# MCU_RS485.net
KiCad netlist of a schematic drawn in Altium Designer
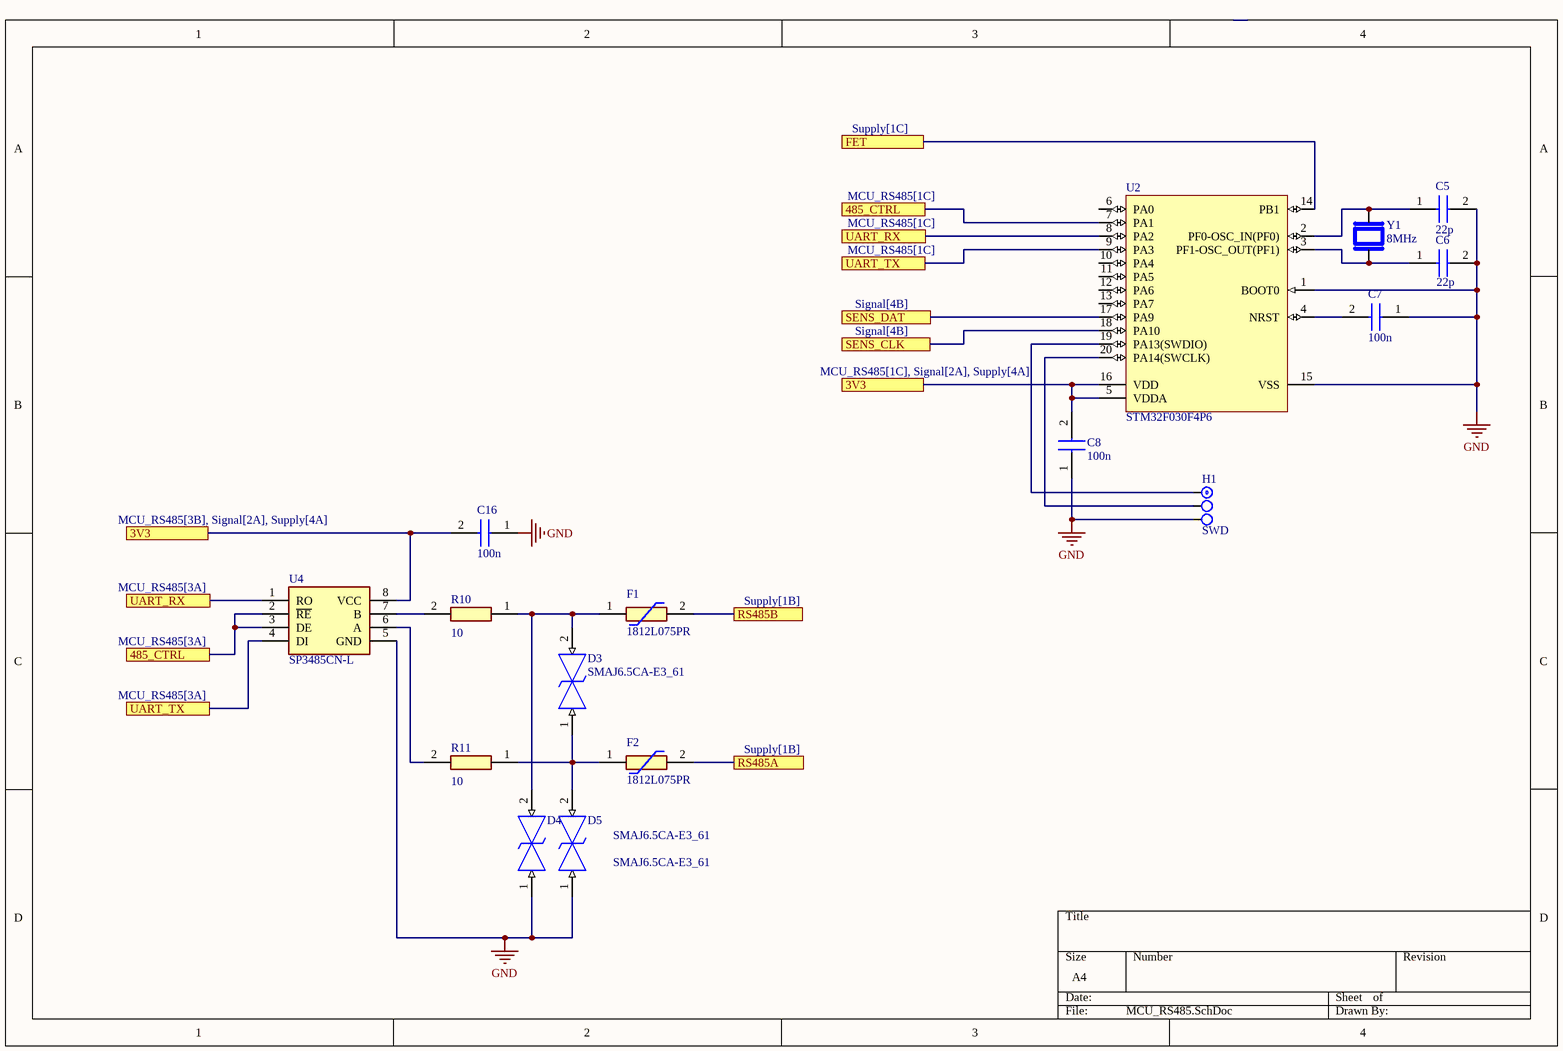
[diagram p0: MCU_RS485.SchDoc]

(export (version "E")
  (design (tool "Eeschema 10.0.6"))
  (components
    (comp (ref "C5")
      (value "22p")
      (footprint "SamacSys:CAPC2012X94N")
      (description "Capacitor")
      (fields
        (field (name "MANUFACTURER_PART_NUMBER") "08055A471FAT4A")
        (field (name "MOUSER PART NUMBER") "581-08055A471FAT4A")
      )
      (libsource (lib "*") (part "08055A471FAT4A"))
    )
    (comp (ref "C6")
      (value "22p")
      (footprint "SamacSys:CAPC2012X94N")
      (description "Capacitor")
      (fields
        (field (name "MANUFACTURER_PART_NUMBER") "08055A471FAT4A")
        (field (name "MOUSER PART NUMBER") "581-08055A471FAT4A")
      )
      (libsource (lib "*") (part "08055A471FAT4A"))
    )
    (comp (ref "C7")
      (value "100n")
      (footprint "SamacSys:CAPC2012X94N")
      (description "Capacitor")
      (fields
        (field (name "MANUFACTURER_PART_NUMBER") "08055A471FAT4A")
        (field (name "MOUSER PART NUMBER") "581-08055A471FAT4A")
      )
      (libsource (lib "*") (part "08055A471FAT4A"))
    )
    (comp (ref "C8")
      (value "100n")
      (footprint "SamacSys:CAPC2012X94N")
      (description "Capacitor")
      (fields
        (field (name "MANUFACTURER_PART_NUMBER") "08055A471FAT4A")
        (field (name "MOUSER PART NUMBER") "581-08055A471FAT4A")
      )
      (libsource (lib "*") (part "08055A471FAT4A"))
    )
    (comp (ref "C16")
      (value "100n")
      (footprint "SamacSys:CAPC2012X94N")
      (description "Capacitor")
      (fields
        (field (name "MANUFACTURER_PART_NUMBER") "08055A471FAT4A")
        (field (name "MOUSER PART NUMBER") "581-08055A471FAT4A")
      )
      (libsource (lib "*") (part "08055A471FAT4A"))
    )
    (comp (ref "D3")
      (value "SMAJ6.5CA-E3_61")
      (footprint "SamacSys:DIONM5127X229N")
      (description "TVS Diode (Bi-directional)")
      (fields
        (field (name "MANUFACTURER_PART_NUMBER") "SMAJ6.5CA-E3/61")
        (field (name "MOUSER PART NUMBER") "625-SMAJ6.5CA-E3")
      )
      (libsource (lib "*") (part "SMAJ6.5CA-E3_61"))
    )
    (comp (ref "D4")
      (value "SMAJ6.5CA-E3_61")
      (footprint "SamacSys:DIONM5127X229N")
      (description "TVS Diode (Bi-directional)")
      (fields
        (field (name "MANUFACTURER_PART_NUMBER") "SMAJ6.5CA-E3/61")
        (field (name "MOUSER PART NUMBER") "625-SMAJ6.5CA-E3")
      )
      (libsource (lib "*") (part "SMAJ6.5CA-E3_61"))
    )
    (comp (ref "D5")
      (value "SMAJ6.5CA-E3_61")
      (footprint "SamacSys:DIONM5127X229N")
      (description "TVS Diode (Bi-directional)")
      (fields
        (field (name "MANUFACTURER_PART_NUMBER") "SMAJ6.5CA-E3/61")
        (field (name "MOUSER PART NUMBER") "625-SMAJ6.5CA-E3")
      )
      (libsource (lib "*") (part "SMAJ6.5CA-E3_61"))
    )
    (comp (ref "F1")
      (value "1812L075PR")
      (footprint "SamacSys:1812L010DR")
      (description "Resettable Fuse")
      (fields (field (name "MOUSER PART NUMBER") "576-1812L075PR"))
      (libsource (lib "*") (part "1812L075PR"))
    )
    (comp (ref "F2")
      (value "1812L075PR")
      (footprint "SamacSys:1812L010DR")
      (description "Resettable Fuse")
      (fields (field (name "MOUSER PART NUMBER") "576-1812L075PR"))
      (libsource (lib "*") (part "1812L075PR"))
    )
    (comp (ref "H1") (value "SWD") (footprint "J1x3") (libsource (lib "PCB_Project") (part "H-1x3")))
    (comp (ref "R10")
      (value "10")
      (footprint "SamacSys:RESC2012X65N")
      (description "Resistor")
      (fields
        (field (name "MANUFACTURER_PART_NUMBER") "CPF0805B102KE1")
        (field (name "MOUSER PART NUMBER") "279-CPF0805B102KE1")
      )
      (libsource (lib "*") (part "CPF0805B102KE1"))
    )
    (comp (ref "R11")
      (value "10")
      (footprint "SamacSys:RESC2012X65N")
      (description "Resistor")
      (fields
        (field (name "MANUFACTURER_PART_NUMBER") "CPF0805B102KE1")
        (field (name "MOUSER PART NUMBER") "279-CPF0805B102KE1")
      )
      (libsource (lib "*") (part "CPF0805B102KE1"))
    )
    (comp (ref "U2")
      (value "STM32F030F4P6")
      (footprint "STM-TSSOP20_L")
      (libsource (lib "PCB_Project") (part "STM32F030F4P6"))
    )
    (comp (ref "U4")
      (value "SP3485CN-L")
      (footprint "SamacSys:SOIC127P600X175-8N")
      (description "Integrated Circuit")
      (fields (field (name "MOUSER PART NUMBER") "701-SP3485CN-L"))
      (libsource (lib "*") (part "SP3485CN-L"))
    )
    (comp (ref "Y1")
      (value "8MHz")
      (footprint "XTAL_ABM3-14.7456MHZ-D2Y-T")
      (description "Ceramic SMD Crystal")
      (fields (field (name "MP") "ABM3-14.7456MHZ-D2Y-T") (field (name "MF") "Abracon"))
      (libsource (lib "ABM3-14.7456MHZ-D2Y-T") (part "ABM3-14.7456MHZ-D2Y-T"))
    )
  )
  (nets
    (net (code "1") (name "/3V3") (class "Default")
      (node (ref "C16") (pin "2") (pinfunction "2_2") (pintype "passive"))
      (node (ref "C8") (pin "2") (pinfunction "2_2") (pintype "passive"))
      (node (ref "U2") (pin "16") (pinfunction "VDD_16") (pintype "power_in"))
      (node (ref "U2") (pin "5") (pinfunction "VDDA_5") (pintype "power_in"))
      (node (ref "U4") (pin "8") (pinfunction "VCC_8") (pintype "passive"))
    )
    (net (code "2") (name "/485_CTRL") (class "Default")
      (node (ref "U2") (pin "7") (pinfunction "PA1_7") (pintype "bidirectional"))
      (node (ref "U4") (pin "2") (pinfunction "~{RE}_2") (pintype "passive"))
      (node (ref "U4") (pin "3") (pinfunction "DE_3") (pintype "passive"))
    )
    (net (code "3") (name "/FET") (class "Default")
      (node (ref "U2") (pin "14") (pinfunction "PB1_14") (pintype "bidirectional"))
    )
    (net (code "4") (name "/RS485A") (class "Default")
      (node (ref "F2") (pin "2") (pinfunction "2_2") (pintype "passive"))
    )
    (net (code "5") (name "/RS485B") (class "Default")
      (node (ref "F1") (pin "2") (pinfunction "2_2") (pintype "passive"))
    )
    (net (code "6") (name "/SENS_CLK") (class "Default")
      (node (ref "U2") (pin "18") (pinfunction "PA10_18") (pintype "bidirectional"))
    )
    (net (code "7") (name "/SENS_DAT") (class "Default")
      (node (ref "U2") (pin "17") (pinfunction "PA9_17") (pintype "bidirectional"))
    )
    (net (code "8") (name "/UART_RX") (class "Default")
      (node (ref "U2") (pin "8") (pinfunction "PA2_8") (pintype "bidirectional"))
      (node (ref "U4") (pin "1") (pinfunction "RO_1") (pintype "passive"))
    )
    (net (code "9") (name "/UART_TX") (class "Default")
      (node (ref "U2") (pin "9") (pinfunction "PA3_9") (pintype "bidirectional"))
      (node (ref "U4") (pin "4") (pinfunction "DI_4") (pintype "passive"))
    )
    (net (code "10") (name "GND") (class "Default")
      (node (ref "C16") (pin "1") (pinfunction "1_1") (pintype "passive"))
      (node (ref "C5") (pin "2") (pinfunction "2_2") (pintype "passive"))
      (node (ref "C6") (pin "2") (pinfunction "2_2") (pintype "passive"))
      (node (ref "C7") (pin "1") (pinfunction "1_1") (pintype "passive"))
      (node (ref "C8") (pin "1") (pinfunction "1_1") (pintype "passive"))
      (node (ref "D4") (pin "1") (pinfunction "1_1") (pintype "input"))
      (node (ref "D5") (pin "1") (pinfunction "1_1") (pintype "input"))
      (node (ref "H1") (pin "3") (pinfunction "3_3") (pintype "passive"))
      (node (ref "U2") (pin "1") (pinfunction "BOOT0_1") (pintype "input"))
      (node (ref "U2") (pin "15") (pinfunction "VSS_15") (pintype "power_in"))
      (node (ref "U4") (pin "5") (pinfunction "GND_5") (pintype "passive"))
    )
    (net (code "11") (name "Net-(D3-Pad1)") (class "Default")
      (node (ref "D3") (pin "1") (pinfunction "1_1") (pintype "input"))
      (node (ref "D5") (pin "2") (pinfunction "2_2") (pintype "input"))
      (node (ref "F2") (pin "1") (pinfunction "1_1") (pintype "passive"))
      (node (ref "R11") (pin "1") (pinfunction "1_1") (pintype "passive"))
    )
    (net (code "12") (name "Net-(D3-Pad2)") (class "Default")
      (node (ref "D3") (pin "2") (pinfunction "2_2") (pintype "input"))
      (node (ref "D4") (pin "2") (pinfunction "2_2") (pintype "input"))
      (node (ref "F1") (pin "1") (pinfunction "1_1") (pintype "passive"))
      (node (ref "R10") (pin "1") (pinfunction "1_1") (pintype "passive"))
    )
    (net (code "13") (name "Net-(U2-NRST)") (class "Default")
      (node (ref "C7") (pin "2") (pinfunction "2_2") (pintype "passive"))
      (node (ref "U2") (pin "4") (pinfunction "NRST_4") (pintype "bidirectional"))
    )
    (net (code "14") (name "Net-(U2-PA13(SWDIO))") (class "Default")
      (node (ref "H1") (pin "1") (pinfunction "1_1") (pintype "passive"))
      (node (ref "U2") (pin "19") (pinfunction "PA13(SWDIO)_19") (pintype "bidirectional"))
    )
    (net (code "15") (name "Net-(U2-PA14(SWCLK))") (class "Default")
      (node (ref "H1") (pin "2") (pinfunction "2_2") (pintype "passive"))
      (node (ref "U2") (pin "20") (pinfunction "PA14(SWCLK)_20") (pintype "bidirectional"))
    )
    (net (code "16") (name "Net-(U2-PF0-OSC_IN(PF0))") (class "Default")
      (node (ref "C5") (pin "1") (pinfunction "1_1") (pintype "passive"))
      (node (ref "U2") (pin "2") (pinfunction "PF0-OSC_IN(PF0)_2") (pintype "bidirectional"))
      (node (ref "Y1") (pin "2") (pinfunction "2_2") (pintype "passive"))
    )
    (net (code "17") (name "Net-(U2-PF1-OSC_OUT(PF1))") (class "Default")
      (node (ref "C6") (pin "1") (pinfunction "1_1") (pintype "passive"))
      (node (ref "U2") (pin "3") (pinfunction "PF1-OSC_OUT(PF1)_3") (pintype "bidirectional"))
      (node (ref "Y1") (pin "1") (pinfunction "1_1") (pintype "passive"))
    )
    (net (code "18") (name "Net-(U4-A)") (class "Default")
      (node (ref "R11") (pin "2") (pinfunction "2_2") (pintype "passive"))
      (node (ref "U4") (pin "6") (pinfunction "A_6") (pintype "passive"))
    )
    (net (code "19") (name "Net-(U4-B)") (class "Default")
      (node (ref "R10") (pin "2") (pinfunction "2_2") (pintype "passive"))
      (node (ref "U4") (pin "7") (pinfunction "B_7") (pintype "passive"))
    )
    (net (code "20") (name "unconnected-(U2-PA0-Pad6)") (class "Default")
      (node (ref "U2") (pin "6") (pinfunction "PA0_6") (pintype "bidirectional"))
    )
    (net (code "21") (name "unconnected-(U2-PA4-Pad10)") (class "Default")
      (node (ref "U2") (pin "10") (pinfunction "PA4_10") (pintype "bidirectional"))
    )
    (net (code "22") (name "unconnected-(U2-PA5-Pad11)") (class "Default")
      (node (ref "U2") (pin "11") (pinfunction "PA5_11") (pintype "bidirectional"))
    )
    (net (code "23") (name "unconnected-(U2-PA6-Pad12)") (class "Default")
      (node (ref "U2") (pin "12") (pinfunction "PA6_12") (pintype "bidirectional"))
    )
    (net (code "24") (name "unconnected-(U2-PA7-Pad13)") (class "Default")
      (node (ref "U2") (pin "13") (pinfunction "PA7_13") (pintype "bidirectional"))
    )
  )
)
